# SiPM_ASSY2.net
KiCad netlist of a schematic drawn in Altium Designer
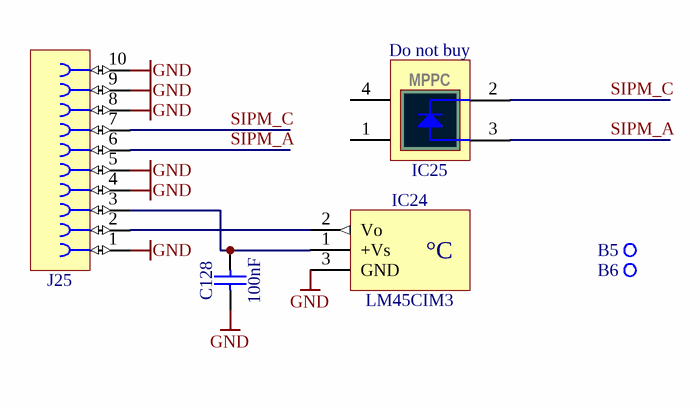
[diagram p0: SiPM_ASSY2.SchDoc]

(export (version "E")
  (design (tool "Eeschema 10.0.6"))
  (components
    (comp (ref "B5")
      (value "Plated Hole")
      (footprint "MTG270_500")
      (description "Single Terminal Socket")
      (fields (field (name "PART NUMBER") "PLATED_HOLE2.7_PAD5.0") (field (name "AUTHOR") "CERN DEM JMW"))
      (libsource (lib "Eletro-mechanical") (part "Single Terminal Socket"))
    )
    (comp (ref "B6")
      (value "Plated Hole")
      (footprint "MTG270_500")
      (description "Single Terminal Socket")
      (fields (field (name "PART NUMBER") "PLATED_HOLE2.7_PAD5.0") (field (name "AUTHOR") "CERN DEM JMW"))
      (libsource (lib "Eletro-mechanical") (part "Single Terminal Socket"))
    )
    (comp (ref "C128")
      (value "100nF")
      (footprint "CAPC1005X55N")
      (description "Non-polarised capacitor")
      (fields
        (field (name "PART NUMBER") "CC0402_100NF_16V_10%_X7R")
        (field (name "VOLTAGE") "16V")
        (field (name "AUTHOR") "CERN DEM JLC")
      )
      (libsource (lib "Capacitors") (part "Capacitor - non polarized"))
    )
    (comp (ref "IC24")
      (value "LM45CIM3")
      (footprint "SOT95P251X112-3N")
      (description "-20° to +100°C ±3°C Precision Centigrade Temperature Sensors")
      (fields (field (name "MANUFACTURER") "NATIONAL SEMICONDUCTOR") (field (name "AUTHOR") "CERN DEM JLC"))
      (libsource (lib "ICs And Semiconductors") (part "LM45"))
    )
    (comp (ref "IC25")
      (value "Do not buy")
      (footprint "HAMAMATSU_S13360-1325PE")
      (description "MPPC (Multi-Pixel Photon Counter)")
      (fields
        (field (name "PART NUMBER") "S13360-1325PE")
        (field (name "MANUFACTURER") "HAMAMATSU")
        (field (name "AUTHOR") "GK")
      )
      (libsource (lib "LIBRARY_SCH") (part "SENS_S13360-1325PE"))
    )
    (comp (ref "J25")
      (value "FFC/FPC")
      (footprint "MOLEX_52745-1097")
      (description "Connector 10 Female")
      (fields
        (field (name "PART NUMBER") "MOLEX_52745-1097")
        (field (name "MANUFACTURER") "MOLEX")
        (field (name "AUTHOR") "CERN DEM JLC")
      )
      (libsource (lib "Connectors") (part "Connector 10 Female"))
    )
  )
  (nets
    (net (code "1") (name "/SIPM_A") (class "Default")
      (node (ref "IC25") (pin "3") (pinfunction "A_3") (pintype "passive"))
      (node (ref "J25") (pin "6") (pinfunction "6_6") (pintype "bidirectional"))
    )
    (net (code "2") (name "/SIPM_C") (class "Default")
      (node (ref "IC25") (pin "2") (pinfunction "C_2") (pintype "passive"))
      (node (ref "J25") (pin "7") (pinfunction "7_7") (pintype "bidirectional"))
    )
    (net (code "3") (name "GND") (class "Default")
      (node (ref "C128") (pin "1") (pinfunction "1_1") (pintype "passive"))
      (node (ref "IC24") (pin "3") (pinfunction "GND_3") (pintype "power_in"))
      (node (ref "J25") (pin "1") (pinfunction "1_1") (pintype "bidirectional"))
      (node (ref "J25") (pin "10") (pinfunction "10_10") (pintype "bidirectional"))
      (node (ref "J25") (pin "4") (pinfunction "4_4") (pintype "bidirectional"))
      (node (ref "J25") (pin "5") (pinfunction "5_5") (pintype "bidirectional"))
      (node (ref "J25") (pin "8") (pinfunction "8_8") (pintype "bidirectional"))
      (node (ref "J25") (pin "9") (pinfunction "9_9") (pintype "bidirectional"))
    )
    (net (code "4") (name "Net-(IC24-+Vs)") (class "Default")
      (node (ref "C128") (pin "2") (pinfunction "2_2") (pintype "passive"))
      (node (ref "IC24") (pin "1") (pinfunction "+Vs_1") (pintype "power_in"))
      (node (ref "J25") (pin "3") (pinfunction "3_3") (pintype "bidirectional"))
    )
    (net (code "5") (name "Net-(IC24-Vo)") (class "Default")
      (node (ref "IC24") (pin "2") (pinfunction "Vo_2") (pintype "output"))
      (node (ref "J25") (pin "2") (pinfunction "2_2") (pintype "bidirectional"))
    )
    (net (code "6") (name "unconnected-(B5-Pad1)") (class "Default")
      (node (ref "B5") (pin "1") (pinfunction "1_1") (pintype "bidirectional"))
    )
    (net (code "7") (name "unconnected-(B6-Pad1)") (class "Default")
      (node (ref "B6") (pin "1") (pinfunction "1_1") (pintype "bidirectional"))
    )
    (net (code "8") (name "unconnected-(IC25-NC-Pad1)") (class "Default")
      (node (ref "IC25") (pin "1") (pinfunction "NC_1") (pintype "passive"))
    )
    (net (code "9") (name "unconnected-(IC25-NC-Pad4)") (class "Default")
      (node (ref "IC25") (pin "4") (pinfunction "NC_4") (pintype "passive"))
    )
  )
)
